# TI_ESP_PCB.net
KiCad netlist of a schematic drawn in EAGLE
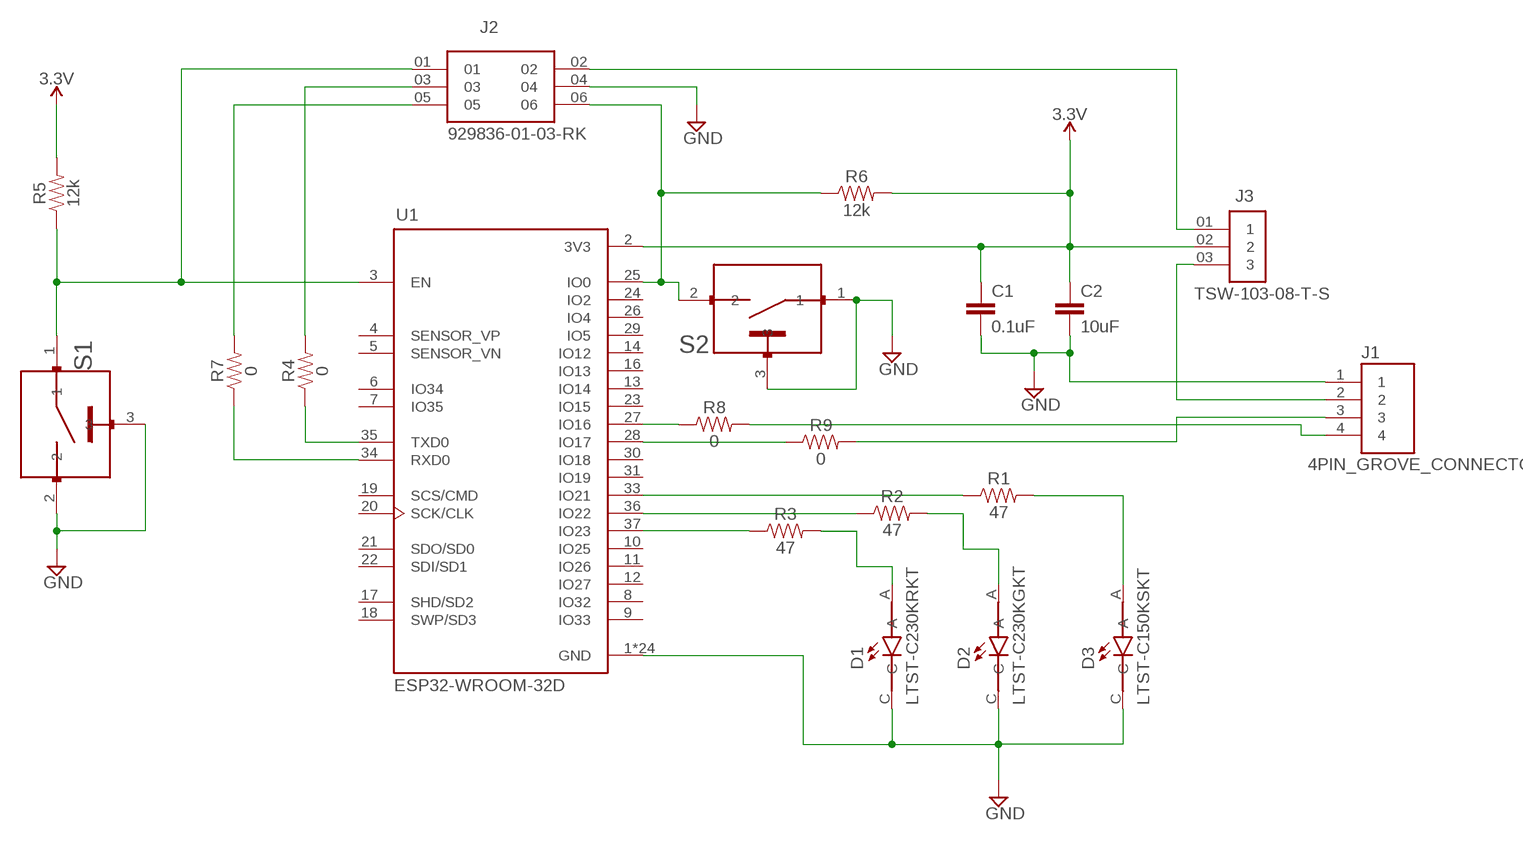
[diagram p0: schematic, sheet 1]

(export (version "E")
  (design (tool "Eeschema 10.0.6"))
  (components
    (comp (ref "C1")
      (value "0.1uF")
      (footprint "eagle-import:1206")
      (libsource (lib "eagle-import") (part "0.1UF-1206"))
    )
    (comp (ref "C2")
      (value "10uF")
      (footprint "eagle-import:1206")
      (libsource (lib "eagle-import") (part "10UF-1206"))
    )
    (comp (ref "D1")
      (value "LTST-C230KRKT")
      (footprint "eagle-import:LEDC3216X110")
      (fields (field (name "MF") "Lite-On Inc."))
      (libsource (lib "eagle-import") (part "LTST-C230KRKT"))
    )
    (comp (ref "D2")
      (value "LTST-C230KGKT")
      (footprint "eagle-import:LEDC3216X110")
      (fields (field (name "MF") "Lite-On Inc."))
      (libsource (lib "eagle-import") (part "LTST-C230KGKT"))
    )
    (comp (ref "D3")
      (value "LTST-C150KSKT")
      (footprint "eagle-import:LEDC3216X110")
      (fields (field (name "MF") "Lite-On Inc."))
      (libsource (lib "eagle-import") (part "LTST-C150KSKT"))
    )
    (comp (ref "J1")
      (value "4PIN_GROVE_CONNECTOR")
      (footprint "eagle-import:SEEED_114020163")
      (fields (field (name "MF") "Seeed Technology Co., Ltd") (field (name "MP") "110990030"))
      (libsource (lib "eagle-import") (part "4PIN_GROVE_CONNECTOR"))
    )
    (comp (ref "J2")
      (value "929836-01-03-RK")
      (footprint "eagle-import:3M-2X3_6PIN_CONNECTOR")
      (fields (field (name "MF") "3M"))
      (libsource (lib "eagle-import") (part "929836-01-03-RK"))
    )
    (comp (ref "J3")
      (value "TSW-103-08-T-S")
      (footprint "eagle-import:SAMTEC_TSW-103-08-T-S")
      (fields (field (name "MF") "Samtec Inc."))
      (libsource (lib "eagle-import") (part "TSW-103-08-T-S"))
    )
    (comp (ref "R1")
      (value "47")
      (footprint "eagle-import:1206")
      (libsource (lib "eagle-import") (part "47OHM"))
    )
    (comp (ref "R2")
      (value "47")
      (footprint "eagle-import:1206")
      (libsource (lib "eagle-import") (part "47OHM"))
    )
    (comp (ref "R3")
      (value "47")
      (footprint "eagle-import:1206")
      (libsource (lib "eagle-import") (part "47OHM"))
    )
    (comp (ref "R4")
      (value "0")
      (footprint "eagle-import:1206")
      (libsource (lib "eagle-import") (part "470OHM"))
    )
    (comp (ref "R5")
      (value "12k")
      (footprint "eagle-import:1206")
      (libsource (lib "eagle-import") (part "12KOHM"))
    )
    (comp (ref "R6")
      (value "12k")
      (footprint "eagle-import:1206")
      (libsource (lib "eagle-import") (part "12KOHM"))
    )
    (comp (ref "R7")
      (value "0")
      (footprint "eagle-import:1206")
      (libsource (lib "eagle-import") (part "470OHM"))
    )
    (comp (ref "R8")
      (value "0")
      (footprint "eagle-import:1206")
      (libsource (lib "eagle-import") (part "470OHM"))
    )
    (comp (ref "R9")
      (value "0")
      (footprint "eagle-import:1206")
      (libsource (lib "eagle-import") (part "470OHM"))
    )
    (comp (ref "S1")
      (value "B3U-1100P")
      (footprint "eagle-import:SW_B3U-1100P")
      (fields (field (name "MF") "Omron"))
      (libsource (lib "eagle-import") (part "B3U-1100P"))
    )
    (comp (ref "S2")
      (value "B3U-1100P")
      (footprint "eagle-import:SW_B3U-1100P")
      (fields (field (name "MF") "Omron"))
      (libsource (lib "eagle-import") (part "B3U-1100P"))
    )
    (comp (ref "U1")
      (value "ESP32-WROOM-32D")
      (footprint "eagle-import:MODULE_ESP32-WROOM-32D")
      (fields (field (name "MF") "Espressif Systems"))
      (libsource (lib "eagle-import") (part "ESP32-WROOM-32D"))
    )
  )
  (nets
    (net (code "1") (name "3.3V") (class "Default")
      (node (ref "C1") (pin "1") (pinfunction "1_1") (pintype "passive"))
      (node (ref "C2") (pin "1") (pinfunction "1_1") (pintype "passive"))
      (node (ref "J3") (pin "02") (pinfunction "2_02") (pintype "passive"))
      (node (ref "R5") (pin "2") (pinfunction "2_2") (pintype "passive"))
      (node (ref "R6") (pin "2") (pinfunction "2_2") (pintype "passive"))
      (node (ref "U1") (pin "2") (pinfunction "3V3_2") (pintype "power_in"))
    )
    (net (code "2") (name "GND") (class "Default")
      (node (ref "C1") (pin "2") (pinfunction "2_2") (pintype "passive"))
      (node (ref "C2") (pin "2") (pinfunction "2_2") (pintype "passive"))
      (node (ref "D1") (pin "C") (pinfunction "C_C") (pintype "passive"))
      (node (ref "D2") (pin "C") (pinfunction "C_C") (pintype "passive"))
      (node (ref "D3") (pin "C") (pinfunction "C_C") (pintype "passive"))
      (node (ref "J1") (pin "1") (pinfunction "1_1") (pintype "passive"))
      (node (ref "J2") (pin "04") (pinfunction "04_04") (pintype "passive"))
      (node (ref "S1") (pin "2") (pinfunction "2_2") (pintype "passive"))
      (node (ref "S1") (pin "3") (pinfunction "3_3") (pintype "passive"))
      (node (ref "S2") (pin "1") (pinfunction "1_1") (pintype "passive"))
      (node (ref "S2") (pin "3") (pinfunction "3_3") (pintype "passive"))
      (node (ref "U1") (pin "1") (pinfunction "GND_1") (pintype "power_in"))
      (node (ref "U1") (pin "15") (pinfunction "GND_15") (pintype "power_in"))
      (node (ref "U1") (pin "38") (pinfunction "GND_38") (pintype "power_in"))
      (node (ref "U1") (pin "39_1") (pinfunction "GND_39_1") (pintype "power_in"))
      (node (ref "U1") (pin "39_10") (pinfunction "GND_39_10") (pintype "power_in"))
      (node (ref "U1") (pin "39_11") (pinfunction "GND_39_11") (pintype "power_in"))
      (node (ref "U1") (pin "39_12") (pinfunction "GND_39_12") (pintype "power_in"))
      (node (ref "U1") (pin "39_13") (pinfunction "GND_39_13") (pintype "power_in"))
      (node (ref "U1") (pin "39_14") (pinfunction "GND_39_14") (pintype "power_in"))
      (node (ref "U1") (pin "39_15") (pinfunction "GND_39_15") (pintype "power_in"))
      (node (ref "U1") (pin "39_16") (pinfunction "GND_39_16") (pintype "power_in"))
      (node (ref "U1") (pin "39_17") (pinfunction "GND_39_17") (pintype "power_in"))
      (node (ref "U1") (pin "39_18") (pinfunction "GND_39_18") (pintype "power_in"))
      (node (ref "U1") (pin "39_19") (pinfunction "GND_39_19") (pintype "power_in"))
      (node (ref "U1") (pin "39_2") (pinfunction "GND_39_2") (pintype "power_in"))
      (node (ref "U1") (pin "39_20") (pinfunction "GND_39_20") (pintype "power_in"))
      (node (ref "U1") (pin "39_21") (pinfunction "GND_39_21") (pintype "power_in"))
      (node (ref "U1") (pin "39_3") (pinfunction "GND_39_3") (pintype "power_in"))
      (node (ref "U1") (pin "39_4") (pinfunction "GND_39_4") (pintype "power_in"))
      (node (ref "U1") (pin "39_5") (pinfunction "GND_39_5") (pintype "power_in"))
      (node (ref "U1") (pin "39_6") (pinfunction "GND_39_6") (pintype "power_in"))
      (node (ref "U1") (pin "39_7") (pinfunction "GND_39_7") (pintype "power_in"))
      (node (ref "U1") (pin "39_8") (pinfunction "GND_39_8") (pintype "power_in"))
      (node (ref "U1") (pin "39_9") (pinfunction "GND_39_9") (pintype "power_in"))
    )
    (net (code "3") (name "Net-(D1-PadA)") (class "Default")
      (node (ref "D1") (pin "A") (pinfunction "A_A") (pintype "passive"))
      (node (ref "R3") (pin "2") (pinfunction "2_2") (pintype "passive"))
    )
    (net (code "4") (name "Net-(D2-PadA)") (class "Default")
      (node (ref "D2") (pin "A") (pinfunction "A_A") (pintype "passive"))
      (node (ref "R2") (pin "2") (pinfunction "2_2") (pintype "passive"))
    )
    (net (code "5") (name "Net-(D3-PadA)") (class "Default")
      (node (ref "D3") (pin "A") (pinfunction "A_A") (pintype "passive"))
      (node (ref "R1") (pin "2") (pinfunction "2_2") (pintype "passive"))
    )
    (net (code "6") (name "Net-(J1-Pad3)") (class "Default")
      (node (ref "J1") (pin "3") (pinfunction "3_3") (pintype "passive"))
      (node (ref "R9") (pin "2") (pinfunction "2_2") (pintype "passive"))
    )
    (net (code "7") (name "Net-(J1-Pad4)") (class "Default")
      (node (ref "J1") (pin "4") (pinfunction "4_4") (pintype "passive"))
      (node (ref "R8") (pin "2") (pinfunction "2_2") (pintype "passive"))
    )
    (net (code "8") (name "Net-(J2-Pad03)") (class "Default")
      (node (ref "J2") (pin "03") (pinfunction "03_03") (pintype "passive"))
      (node (ref "R4") (pin "2") (pinfunction "2_2") (pintype "passive"))
    )
    (net (code "9") (name "Net-(J2-Pad05)") (class "Default")
      (node (ref "J2") (pin "05") (pinfunction "05_05") (pintype "passive"))
      (node (ref "R7") (pin "2") (pinfunction "2_2") (pintype "passive"))
    )
    (net (code "10") (name "Net-(J3-1)") (class "Default")
      (node (ref "J2") (pin "02") (pinfunction "02_02") (pintype "passive"))
      (node (ref "J3") (pin "01") (pinfunction "1_01") (pintype "passive"))
    )
    (net (code "11") (name "Net-(J3-3)") (class "Default")
      (node (ref "J1") (pin "2") (pinfunction "2_2") (pintype "passive"))
      (node (ref "J3") (pin "03") (pinfunction "3_03") (pintype "passive"))
    )
    (net (code "12") (name "Net-(U1-EN)") (class "Default")
      (node (ref "J2") (pin "01") (pinfunction "01_01") (pintype "passive"))
      (node (ref "R5") (pin "1") (pinfunction "1_1") (pintype "passive"))
      (node (ref "S1") (pin "1") (pinfunction "1_1") (pintype "passive"))
      (node (ref "U1") (pin "3") (pinfunction "EN_3") (pintype "input"))
    )
    (net (code "13") (name "Net-(U1-IO0)") (class "Default")
      (node (ref "J2") (pin "06") (pinfunction "06_06") (pintype "passive"))
      (node (ref "R6") (pin "1") (pinfunction "1_1") (pintype "passive"))
      (node (ref "S2") (pin "2") (pinfunction "2_2") (pintype "passive"))
      (node (ref "U1") (pin "25") (pinfunction "IO0_25") (pintype "bidirectional"))
    )
    (net (code "14") (name "Net-(U1-IO16)") (class "Default")
      (node (ref "R8") (pin "1") (pinfunction "1_1") (pintype "passive"))
      (node (ref "U1") (pin "27") (pinfunction "IO16_27") (pintype "bidirectional"))
    )
    (net (code "15") (name "Net-(U1-IO17)") (class "Default")
      (node (ref "R9") (pin "1") (pinfunction "1_1") (pintype "passive"))
      (node (ref "U1") (pin "28") (pinfunction "IO17_28") (pintype "bidirectional"))
    )
    (net (code "16") (name "Net-(U1-IO21)") (class "Default")
      (node (ref "R1") (pin "1") (pinfunction "1_1") (pintype "passive"))
      (node (ref "U1") (pin "33") (pinfunction "IO21_33") (pintype "bidirectional"))
    )
    (net (code "17") (name "Net-(U1-IO22)") (class "Default")
      (node (ref "R2") (pin "1") (pinfunction "1_1") (pintype "passive"))
      (node (ref "U1") (pin "36") (pinfunction "IO22_36") (pintype "bidirectional"))
    )
    (net (code "18") (name "Net-(U1-IO23)") (class "Default")
      (node (ref "R3") (pin "1") (pinfunction "1_1") (pintype "passive"))
      (node (ref "U1") (pin "37") (pinfunction "IO23_37") (pintype "bidirectional"))
    )
    (net (code "19") (name "Net-(U1-RXD0)") (class "Default")
      (node (ref "R7") (pin "1") (pinfunction "1_1") (pintype "passive"))
      (node (ref "U1") (pin "34") (pinfunction "RXD0_34") (pintype "bidirectional"))
    )
    (net (code "20") (name "Net-(U1-TXD0)") (class "Default")
      (node (ref "R4") (pin "1") (pinfunction "1_1") (pintype "passive"))
      (node (ref "U1") (pin "35") (pinfunction "TXD0_35") (pintype "bidirectional"))
    )
    (net (code "21") (name "unconnected-(U1-IO2-Pad24)") (class "Default")
      (node (ref "U1") (pin "24") (pinfunction "IO2_24") (pintype "bidirectional"))
    )
    (net (code "22") (name "unconnected-(U1-IO4-Pad26)") (class "Default")
      (node (ref "U1") (pin "26") (pinfunction "IO4_26") (pintype "bidirectional"))
    )
    (net (code "23") (name "unconnected-(U1-IO5-Pad29)") (class "Default")
      (node (ref "U1") (pin "29") (pinfunction "IO5_29") (pintype "bidirectional"))
    )
    (net (code "24") (name "unconnected-(U1-IO12-Pad14)") (class "Default")
      (node (ref "U1") (pin "14") (pinfunction "IO12_14") (pintype "bidirectional"))
    )
    (net (code "25") (name "unconnected-(U1-IO13-Pad16)") (class "Default")
      (node (ref "U1") (pin "16") (pinfunction "IO13_16") (pintype "bidirectional"))
    )
    (net (code "26") (name "unconnected-(U1-IO14-Pad13)") (class "Default")
      (node (ref "U1") (pin "13") (pinfunction "IO14_13") (pintype "bidirectional"))
    )
    (net (code "27") (name "unconnected-(U1-IO15-Pad23)") (class "Default")
      (node (ref "U1") (pin "23") (pinfunction "IO15_23") (pintype "bidirectional"))
    )
    (net (code "28") (name "unconnected-(U1-IO18-Pad30)") (class "Default")
      (node (ref "U1") (pin "30") (pinfunction "IO18_30") (pintype "bidirectional"))
    )
    (net (code "29") (name "unconnected-(U1-IO19-Pad31)") (class "Default")
      (node (ref "U1") (pin "31") (pinfunction "IO19_31") (pintype "bidirectional"))
    )
    (net (code "30") (name "unconnected-(U1-IO25-Pad10)") (class "Default")
      (node (ref "U1") (pin "10") (pinfunction "IO25_10") (pintype "bidirectional"))
    )
    (net (code "31") (name "unconnected-(U1-IO26-Pad11)") (class "Default")
      (node (ref "U1") (pin "11") (pinfunction "IO26_11") (pintype "bidirectional"))
    )
    (net (code "32") (name "unconnected-(U1-IO27-Pad12)") (class "Default")
      (node (ref "U1") (pin "12") (pinfunction "IO27_12") (pintype "bidirectional"))
    )
    (net (code "33") (name "unconnected-(U1-IO32-Pad8)") (class "Default")
      (node (ref "U1") (pin "8") (pinfunction "IO32_8") (pintype "bidirectional"))
    )
    (net (code "34") (name "unconnected-(U1-IO33-Pad9)") (class "Default")
      (node (ref "U1") (pin "9") (pinfunction "IO33_9") (pintype "bidirectional"))
    )
    (net (code "35") (name "unconnected-(U1-IO34-Pad6)") (class "Default")
      (node (ref "U1") (pin "6") (pinfunction "IO34_6") (pintype "input"))
    )
    (net (code "36") (name "unconnected-(U1-IO35-Pad7)") (class "Default")
      (node (ref "U1") (pin "7") (pinfunction "IO35_7") (pintype "input"))
    )
    (net (code "37") (name "unconnected-(U1-SCK{slash}CLK-Pad20)") (class "Default")
      (node (ref "U1") (pin "20") (pinfunction "SCK/CLK_20") (pintype "bidirectional"))
    )
    (net (code "38") (name "unconnected-(U1-SCS{slash}CMD-Pad19)") (class "Default")
      (node (ref "U1") (pin "19") (pinfunction "SCS/CMD_19") (pintype "bidirectional"))
    )
    (net (code "39") (name "unconnected-(U1-SDI{slash}SD1-Pad22)") (class "Default")
      (node (ref "U1") (pin "22") (pinfunction "SDI/SD1_22") (pintype "bidirectional"))
    )
    (net (code "40") (name "unconnected-(U1-SDO{slash}SD0-Pad21)") (class "Default")
      (node (ref "U1") (pin "21") (pinfunction "SDO/SD0_21") (pintype "bidirectional"))
    )
    (net (code "41") (name "unconnected-(U1-SENSOR_VN-Pad5)") (class "Default")
      (node (ref "U1") (pin "5") (pinfunction "SENSOR_VN_5") (pintype "input"))
    )
    (net (code "42") (name "unconnected-(U1-SENSOR_VP-Pad4)") (class "Default")
      (node (ref "U1") (pin "4") (pinfunction "SENSOR_VP_4") (pintype "input"))
    )
    (net (code "43") (name "unconnected-(U1-SHD{slash}SD2-Pad17)") (class "Default")
      (node (ref "U1") (pin "17") (pinfunction "SHD/SD2_17") (pintype "bidirectional"))
    )
    (net (code "44") (name "unconnected-(U1-SWP{slash}SD3-Pad18)") (class "Default")
      (node (ref "U1") (pin "18") (pinfunction "SWP/SD3_18") (pintype "bidirectional"))
    )
  )
)
